# tulip_breakout.net
KiCad netlist of a schematic drawn in EAGLE
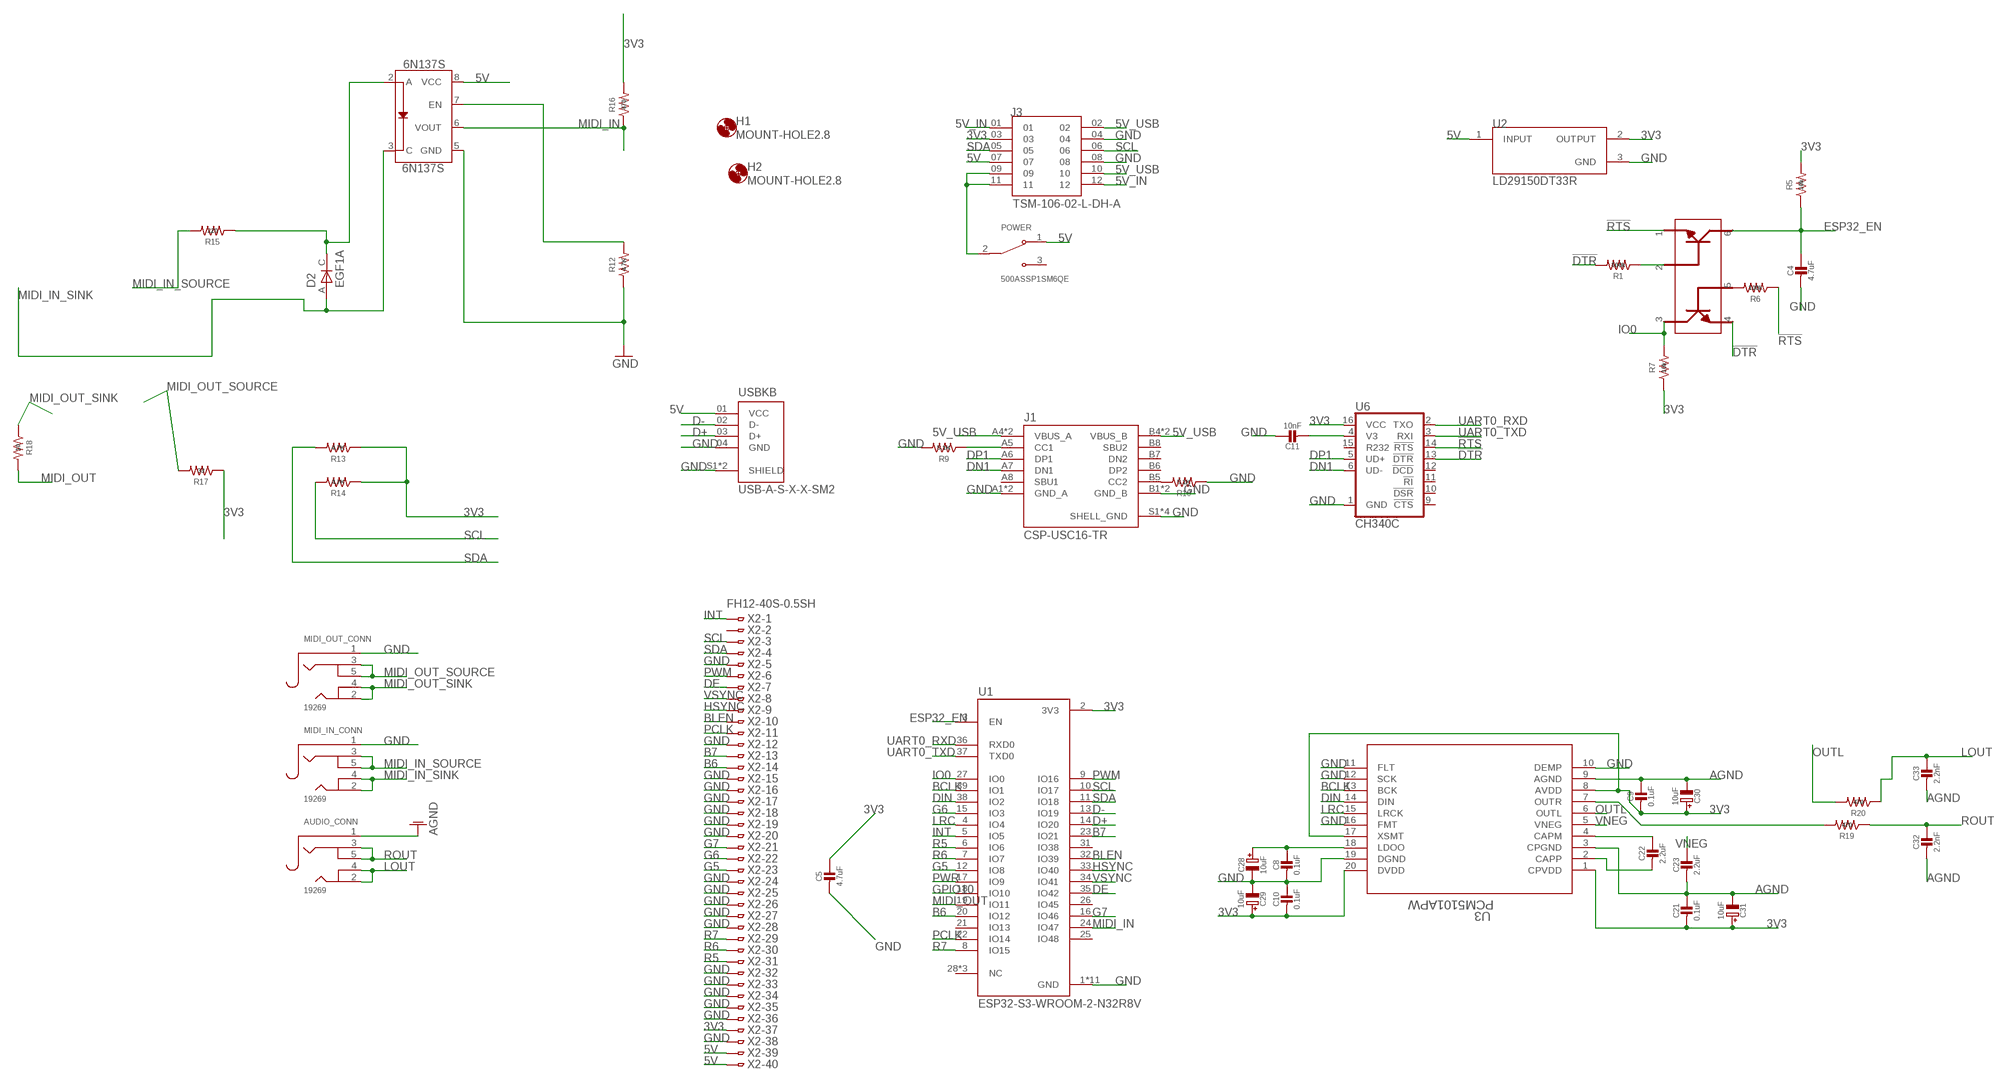
[diagram p0: schematic, sheet 1]

(export (version "E")
  (design (tool "Eeschema 10.0.6"))
  (components
    (comp (ref "6N137S")
      (value "6N137S")
      (footprint "eagle-import:8-SMD")
      (fields (field (name "MF") "Lite-On Inc."))
      (libsource (lib "eagle-import") (part "6N137S"))
    )
    (comp (ref "AUDIO_CONN")
      (value "19269")
      (footprint "eagle-import:4UCONN_19269")
      (libsource (lib "eagle-import") (part "AUDIO_3.5MMJACK"))
    )
    (comp (ref "C4")
      (value "4.7uF")
      (footprint "eagle-import:0805-NO")
      (libsource (lib "eagle-import") (part "CAP_CERAMIC0805-NOOUTLINE"))
    )
    (comp (ref "C5")
      (value "4.7uF")
      (footprint "eagle-import:0805-NO")
      (libsource (lib "eagle-import") (part "CAP_CERAMIC0805-NOOUTLINE"))
    )
    (comp (ref "C8")
      (value "0.1uF")
      (footprint "eagle-import:0805-NO")
      (libsource (lib "eagle-import") (part "CAP_CERAMIC0805-NOOUTLINE"))
    )
    (comp (ref "C9")
      (value "0.1uF")
      (footprint "eagle-import:0805-NO")
      (libsource (lib "eagle-import") (part "CAP_CERAMIC0805-NOOUTLINE"))
    )
    (comp (ref "C10")
      (value "0.1uF")
      (footprint "eagle-import:0805-NO")
      (libsource (lib "eagle-import") (part "CAP_CERAMIC0805-NOOUTLINE"))
    )
    (comp (ref "C11")
      (value "10nF")
      (footprint "eagle-import:0805-NO")
      (libsource (lib "eagle-import") (part "CAP_CERAMIC0805-NOOUTLINE"))
    )
    (comp (ref "C21")
      (value "0.1uF")
      (footprint "eagle-import:0805-NO")
      (libsource (lib "eagle-import") (part "CAP_CERAMIC0805-NOOUTLINE"))
    )
    (comp (ref "C22")
      (value "2.2uF")
      (footprint "eagle-import:0805-NO")
      (libsource (lib "eagle-import") (part "CAP_CERAMIC0805-NOOUTLINE"))
    )
    (comp (ref "C23")
      (value "2.2uF")
      (footprint "eagle-import:0805-NO")
      (libsource (lib "eagle-import") (part "CAP_CERAMIC0805-NOOUTLINE"))
    )
    (comp (ref "C28")
      (value "10uF")
      (footprint "eagle-import:PANASONIC_C")
      (libsource (lib "eagle-import") (part "CAP_ELECTROLYTICPANASONIC_C"))
    )
    (comp (ref "C29")
      (value "10uF")
      (footprint "eagle-import:PANASONIC_C")
      (libsource (lib "eagle-import") (part "CAP_ELECTROLYTICPANASONIC_C"))
    )
    (comp (ref "C30")
      (value "10uF")
      (footprint "eagle-import:PANASONIC_C")
      (libsource (lib "eagle-import") (part "CAP_ELECTROLYTICPANASONIC_C"))
    )
    (comp (ref "C31")
      (value "10uF")
      (footprint "eagle-import:PANASONIC_C")
      (libsource (lib "eagle-import") (part "CAP_ELECTROLYTICPANASONIC_C"))
    )
    (comp (ref "C32")
      (value "2.2nF")
      (footprint "eagle-import:0805-NO")
      (libsource (lib "eagle-import") (part "CAP_CERAMIC0805-NOOUTLINE"))
    )
    (comp (ref "C33")
      (value "2.2nF")
      (footprint "eagle-import:0805-NO")
      (libsource (lib "eagle-import") (part "CAP_CERAMIC0805-NOOUTLINE"))
    )
    (comp (ref "D2")
      (value "EGF1A")
      (footprint "eagle-import:DIOM449X264X300L114X135N")
      (fields (field (name "MF") "ON Semiconductor"))
      (libsource (lib "eagle-import") (part "EGF1A"))
    )
    (comp (ref "H1")
      (value "MOUNT-HOLE2.8")
      (footprint "eagle-import:2,8")
      (libsource (lib "eagle-import") (part "MOUNT-HOLE2.8"))
    )
    (comp (ref "H2")
      (value "MOUNT-HOLE2.8")
      (footprint "eagle-import:2,8")
      (libsource (lib "eagle-import") (part "MOUNT-HOLE2.8"))
    )
    (comp (ref "J1")
      (value "CSP-USC16-TR")
      (footprint "eagle-import:VALCON_CSP-USC16-TR")
      (fields (field (name "MF") "Valcon"))
      (libsource (lib "eagle-import") (part "CSP-USC16-TR"))
    )
    (comp (ref "J3")
      (value "TSM-106-02-L-DH-A")
      (footprint "eagle-import:SAMTEC_TSM-106-02-L-DH-A")
      (fields (field (name "DIGI-KEY_PART_NUMBER") "612-TSM-106-02-L-DH-A-ND") (field (name "MF") "Samtec"))
      (libsource (lib "eagle-import") (part "TSM-106-02-L-DH-A"))
    )
    (comp (ref "MIDI_IN_CONN")
      (value "19269")
      (footprint "eagle-import:4UCONN_19269")
      (libsource (lib "eagle-import") (part "AUDIO_3.5MMJACK"))
    )
    (comp (ref "MIDI_OUT_CONN")
      (value "19269")
      (footprint "eagle-import:4UCONN_19269")
      (libsource (lib "eagle-import") (part "AUDIO_3.5MMJACK"))
    )
    (comp (ref "POWER")
      (value "500ASSP1SM6QE")
      (footprint "eagle-import:SW_500ASSP1SM6QE")
      (fields (field (name "DIGI-KEY_PART_NUMBER") "EG5810TR-ND") (field (name "MF") "E-Switch"))
      (libsource (lib "eagle-import") (part "500ASSP1SM6QE"))
    )
    (comp (ref "R1")
      (value "100k")
      (footprint "eagle-import:R0805")
      (libsource (lib "eagle-import") (part "R-US_R0805"))
    )
    (comp (ref "R5")
      (value "10k")
      (footprint "eagle-import:R0805")
      (libsource (lib "eagle-import") (part "R-US_R0805"))
    )
    (comp (ref "R6")
      (value "100k")
      (footprint "eagle-import:R0805")
      (libsource (lib "eagle-import") (part "R-US_R0805"))
    )
    (comp (ref "R7")
      (value "10k")
      (footprint "eagle-import:R0805")
      (libsource (lib "eagle-import") (part "R-US_R0805"))
    )
    (comp (ref "R9")
      (value "5.1K")
      (footprint "eagle-import:R0805")
      (libsource (lib "eagle-import") (part "R-US_R0805"))
    )
    (comp (ref "R10")
      (value "5.1K")
      (footprint "eagle-import:R0805")
      (libsource (lib "eagle-import") (part "R-US_R0805"))
    )
    (comp (ref "R12")
      (value "4.7K")
      (footprint "eagle-import:R0805")
      (libsource (lib "eagle-import") (part "R-US_R0805"))
    )
    (comp (ref "R13")
      (value "4.7K")
      (footprint "eagle-import:R0805")
      (libsource (lib "eagle-import") (part "R-US_R0805"))
    )
    (comp (ref "R14")
      (value "4.7K")
      (footprint "eagle-import:R0805")
      (libsource (lib "eagle-import") (part "R-US_R0805"))
    )
    (comp (ref "R15")
      (value "220")
      (footprint "eagle-import:R0805")
      (libsource (lib "eagle-import") (part "R-US_R0805"))
    )
    (comp (ref "R16")
      (value "470")
      (footprint "eagle-import:R0805")
      (libsource (lib "eagle-import") (part "R-US_R0805"))
    )
    (comp (ref "R17")
      (value "33")
      (footprint "eagle-import:R0805")
      (libsource (lib "eagle-import") (part "R-US_R0805"))
    )
    (comp (ref "R18")
      (value "10")
      (footprint "eagle-import:R0805")
      (libsource (lib "eagle-import") (part "R-US_R0805"))
    )
    (comp (ref "R19")
      (value "470")
      (footprint "eagle-import:R0805")
      (libsource (lib "eagle-import") (part "R-US_R0805"))
    )
    (comp (ref "R20")
      (value "470")
      (footprint "eagle-import:R0805")
      (libsource (lib "eagle-import") (part "R-US_R0805"))
    )
    (comp (ref "RESET")
      (value "MBT3904DW1T1G")
      (footprint "eagle-import:SOT236")
      (fields (field (name "MF") "ON Semiconductor"))
      (libsource (lib "eagle-import") (part "MBT3904DW1T1G"))
    )
    (comp (ref "U1")
      (value "ESP32-S3-WROOM-2-N32R8V")
      (footprint "eagle-import:XCVR_ESP32-S3-WROOM-2-N32R8V")
      (fields (field (name "MF") "Espressif Systems"))
      (libsource (lib "eagle-import") (part "ESP32-S3-WROOM-2-N32R8V"))
    )
    (comp (ref "U2")
      (value "LD29150DT33R")
      (footprint "eagle-import:DPAK456P972X240-3N")
      (fields (field (name "DIGI-KEY_PART_NUMBER") "497-1496-2-ND") (field (name "MF") "STMicroelectronics"))
      (libsource (lib "eagle-import") (part "LD29150DT33R"))
    )
    (comp (ref "U3")
      (value "PCM5101APW")
      (footprint "eagle-import:PW20_TEX")
      (fields (field (name "COPYRIGHT") "Copyright (C) 2022 Ultra Librarian. All rights reserved."))
      (libsource (lib "eagle-import") (part "PCM5101APW"))
    )
    (comp (ref "U6")
      (value "CH340C")
      (footprint "eagle-import:SO016")
      (libsource (lib "eagle-import") (part "CH340C"))
    )
    (comp (ref "USBKB")
      (value "USB-A-S-X-X-SM2")
      (footprint "eagle-import:SAMTEC_USB-A-S-X-X-SM2")
      (fields (field (name "MF") "Samtec") (field (name "MP") "USB-A-S-F-W-SM2-TR"))
      (libsource (lib "eagle-import") (part "USB-A-S-X-X-SM2"))
    )
    (comp (ref "X2")
      (value "FH12-40S-0.5SH")
      (footprint "eagle-import:FH12-40S-0.5SH")
      (fields (field (name "MPN") "FH12-40S-0.5SH(55)"))
      (libsource (lib "eagle-import") (part "FH12-40S-0.5SH"))
    )
  )
  (nets
    (net (code "1") (name "/3V3") (class "Default")
      (node (ref "C10") (pin "2") (pinfunction "2_2") (pintype "passive"))
      (node (ref "C21") (pin "2") (pinfunction "2_2") (pintype "passive"))
      (node (ref "C29") (pin "+") (pinfunction "+_+") (pintype "passive"))
      (node (ref "C30") (pin "+") (pinfunction "+_+") (pintype "passive"))
      (node (ref "C31") (pin "+") (pinfunction "+_+") (pintype "passive"))
      (node (ref "C5") (pin "1") (pinfunction "1_1") (pintype "passive"))
      (node (ref "C9") (pin "2") (pinfunction "2_2") (pintype "passive"))
      (node (ref "J3") (pin "03") (pinfunction "03_03") (pintype "passive"))
      (node (ref "R13") (pin "1") (pinfunction "1_1") (pintype "passive"))
      (node (ref "R14") (pin "1") (pinfunction "1_1") (pintype "passive"))
      (node (ref "R16") (pin "2") (pinfunction "2_2") (pintype "passive"))
      (node (ref "R17") (pin "1") (pinfunction "1_1") (pintype "passive"))
      (node (ref "R5") (pin "2") (pinfunction "2_2") (pintype "passive"))
      (node (ref "R7") (pin "1") (pinfunction "1_1") (pintype "passive"))
      (node (ref "U1") (pin "2") (pinfunction "3V3_2") (pintype "power_in"))
      (node (ref "U2") (pin "2") (pinfunction "OUTPUT_2") (pintype "output"))
      (node (ref "U3") (pin "1") (pinfunction "CPVDD_1") (pintype "power_in"))
      (node (ref "U3") (pin "17") (pinfunction "XSMT_17") (pintype "input"))
      (node (ref "U3") (pin "20") (pinfunction "DVDD_20") (pintype "power_in"))
      (node (ref "U3") (pin "8") (pinfunction "AVDD_8") (pintype "power_in"))
      (node (ref "U6") (pin "16") (pinfunction "VCC_16") (pintype "bidirectional"))
      (node (ref "X2") (pin "37") (pinfunction "1_37") (pintype "passive"))
    )
    (net (code "2") (name "/5V") (class "Default")
      (node (ref "6N137S") (pin "8") (pinfunction "VCC_8") (pintype "bidirectional"))
      (node (ref "J3") (pin "07") (pinfunction "07_07") (pintype "passive"))
      (node (ref "POWER") (pin "1") (pinfunction "NC_1") (pintype "passive"))
      (node (ref "U2") (pin "1") (pinfunction "INPUT_1") (pintype "input"))
      (node (ref "USBKB") (pin "01") (pinfunction "VCC_01") (pintype "power_in"))
      (node (ref "X2") (pin "39") (pinfunction "1_39") (pintype "passive"))
      (node (ref "X2") (pin "40") (pinfunction "1_40") (pintype "passive"))
    )
    (net (code "3") (name "/5V_IN") (class "Default")
      (node (ref "J3") (pin "01") (pinfunction "01_01") (pintype "passive"))
      (node (ref "J3") (pin "12") (pinfunction "12_12") (pintype "passive"))
    )
    (net (code "4") (name "/5V_USB") (class "Default")
      (node (ref "J1") (pin "A4") (pinfunction "VBUS_A_A4") (pintype "power_in"))
      (node (ref "J1") (pin "A9") (pinfunction "VBUS_A_A9") (pintype "power_in"))
      (node (ref "J1") (pin "B4") (pinfunction "VBUS_B_B4") (pintype "power_in"))
      (node (ref "J1") (pin "B9") (pinfunction "VBUS_B_B9") (pintype "power_in"))
      (node (ref "J3") (pin "02") (pinfunction "02_02") (pintype "passive"))
      (node (ref "J3") (pin "10") (pinfunction "10_10") (pintype "passive"))
    )
    (net (code "5") (name "/B6") (class "Default")
      (node (ref "U1") (pin "20") (pinfunction "IO12_20") (pintype "bidirectional"))
      (node (ref "X2") (pin "14") (pinfunction "1_14") (pintype "passive"))
    )
    (net (code "6") (name "/B7") (class "Default")
      (node (ref "U1") (pin "23") (pinfunction "IO21_23") (pintype "bidirectional"))
      (node (ref "X2") (pin "13") (pinfunction "1_13") (pintype "passive"))
    )
    (net (code "7") (name "/BCLK") (class "Default")
      (node (ref "U1") (pin "39") (pinfunction "IO1_39") (pintype "bidirectional"))
      (node (ref "U3") (pin "13") (pinfunction "BCK_13") (pintype "input"))
    )
    (net (code "8") (name "/BLEN") (class "Default")
      (node (ref "U1") (pin "32") (pinfunction "IO39_32") (pintype "bidirectional"))
      (node (ref "X2") (pin "10") (pinfunction "1_10") (pintype "passive"))
    )
    (net (code "9") (name "/D+") (class "Default")
      (node (ref "U1") (pin "14") (pinfunction "IO20_14") (pintype "bidirectional"))
      (node (ref "USBKB") (pin "03") (pinfunction "D+_03") (pintype "bidirectional"))
    )
    (net (code "10") (name "/D-") (class "Default")
      (node (ref "U1") (pin "13") (pinfunction "IO19_13") (pintype "bidirectional"))
      (node (ref "USBKB") (pin "02") (pinfunction "D-_02") (pintype "bidirectional"))
    )
    (net (code "11") (name "/DE") (class "Default")
      (node (ref "U1") (pin "35") (pinfunction "IO42_35") (pintype "bidirectional"))
      (node (ref "X2") (pin "7") (pinfunction "1_7") (pintype "passive"))
    )
    (net (code "12") (name "/DIN") (class "Default")
      (node (ref "U1") (pin "38") (pinfunction "IO2_38") (pintype "bidirectional"))
      (node (ref "U3") (pin "14") (pinfunction "DIN_14") (pintype "input"))
    )
    (net (code "13") (name "/DN1") (class "Default")
      (node (ref "J1") (pin "A7") (pinfunction "DN1_A7") (pintype "bidirectional"))
      (node (ref "U6") (pin "6") (pinfunction "UD-_6") (pintype "bidirectional"))
    )
    (net (code "14") (name "/DP1") (class "Default")
      (node (ref "J1") (pin "A6") (pinfunction "DP1_A6") (pintype "bidirectional"))
      (node (ref "U6") (pin "5") (pinfunction "UD+_5") (pintype "bidirectional"))
    )
    (net (code "15") (name "/ESP32_EN") (class "Default")
      (node (ref "C4") (pin "1") (pinfunction "1_1") (pintype "passive"))
      (node (ref "R5") (pin "1") (pinfunction "1_1") (pintype "passive"))
      (node (ref "RESET") (pin "6") (pinfunction "6_6") (pintype "bidirectional"))
      (node (ref "U1") (pin "3") (pinfunction "EN_3") (pintype "input"))
    )
    (net (code "16") (name "/G5") (class "Default")
      (node (ref "U1") (pin "12") (pinfunction "IO8_12") (pintype "bidirectional"))
      (node (ref "X2") (pin "23") (pinfunction "1_23") (pintype "passive"))
    )
    (net (code "17") (name "/G6") (class "Default")
      (node (ref "U1") (pin "15") (pinfunction "IO3_15") (pintype "bidirectional"))
      (node (ref "X2") (pin "22") (pinfunction "1_22") (pintype "passive"))
    )
    (net (code "18") (name "/G7") (class "Default")
      (node (ref "U1") (pin "16") (pinfunction "IO46_16") (pintype "bidirectional"))
      (node (ref "X2") (pin "21") (pinfunction "1_21") (pintype "passive"))
    )
    (net (code "19") (name "/GPIO10") (class "Default")
      (node (ref "U1") (pin "18") (pinfunction "IO10_18") (pintype "bidirectional"))
    )
    (net (code "20") (name "/HSYNC") (class "Default")
      (node (ref "U1") (pin "33") (pinfunction "IO40_33") (pintype "bidirectional"))
      (node (ref "X2") (pin "9") (pinfunction "1_9") (pintype "passive"))
    )
    (net (code "21") (name "/INT") (class "Default")
      (node (ref "U1") (pin "5") (pinfunction "IO5_5") (pintype "bidirectional"))
      (node (ref "X2") (pin "1") (pinfunction "1_1") (pintype "passive"))
    )
    (net (code "22") (name "/IO0") (class "Default")
      (node (ref "R7") (pin "2") (pinfunction "2_2") (pintype "passive"))
      (node (ref "RESET") (pin "3") (pinfunction "3_3") (pintype "bidirectional"))
      (node (ref "U1") (pin "27") (pinfunction "IO0_27") (pintype "bidirectional"))
    )
    (net (code "23") (name "/LOUT") (class "Default")
      (node (ref "AUDIO_CONN") (pin "2") (pinfunction "P$5_2") (pintype "bidirectional"))
      (node (ref "AUDIO_CONN") (pin "4") (pinfunction "P$4_4") (pintype "bidirectional"))
      (node (ref "C33") (pin "1") (pinfunction "1_1") (pintype "passive"))
      (node (ref "R20") (pin "1") (pinfunction "1_1") (pintype "passive"))
    )
    (net (code "24") (name "/LRC") (class "Default")
      (node (ref "U1") (pin "4") (pinfunction "IO4_4") (pintype "bidirectional"))
      (node (ref "U3") (pin "15") (pinfunction "LRCK_15") (pintype "input"))
    )
    (net (code "25") (name "/MIDI_IN") (class "Default")
      (node (ref "6N137S") (pin "6") (pinfunction "VOUT_6") (pintype "bidirectional"))
      (node (ref "R16") (pin "1") (pinfunction "1_1") (pintype "passive"))
      (node (ref "U1") (pin "24") (pinfunction "IO47_24") (pintype "bidirectional"))
    )
    (net (code "26") (name "/MIDI_IN_SINK") (class "Default")
      (node (ref "6N137S") (pin "3") (pinfunction "C_3") (pintype "bidirectional"))
      (node (ref "D2") (pin "A") (pinfunction "A_A") (pintype "passive"))
      (node (ref "MIDI_IN_CONN") (pin "2") (pinfunction "P$5_2") (pintype "bidirectional"))
      (node (ref "MIDI_IN_CONN") (pin "4") (pinfunction "P$4_4") (pintype "bidirectional"))
    )
    (net (code "27") (name "/MIDI_IN_SOURCE") (class "Default")
      (node (ref "MIDI_IN_CONN") (pin "3") (pinfunction "P$2_3") (pintype "bidirectional"))
      (node (ref "MIDI_IN_CONN") (pin "5") (pinfunction "P$3_5") (pintype "bidirectional"))
      (node (ref "R15") (pin "2") (pinfunction "2_2") (pintype "passive"))
    )
    (net (code "28") (name "/MIDI_OUT") (class "Default")
      (node (ref "R18") (pin "2") (pinfunction "2_2") (pintype "passive"))
      (node (ref "U1") (pin "19") (pinfunction "IO11_19") (pintype "bidirectional"))
    )
    (net (code "29") (name "/MIDI_OUT_SINK") (class "Default")
      (node (ref "MIDI_OUT_CONN") (pin "2") (pinfunction "P$5_2") (pintype "bidirectional"))
      (node (ref "MIDI_OUT_CONN") (pin "4") (pinfunction "P$4_4") (pintype "bidirectional"))
      (node (ref "R18") (pin "1") (pinfunction "1_1") (pintype "passive"))
    )
    (net (code "30") (name "/MIDI_OUT_SOURCE") (class "Default")
      (node (ref "MIDI_OUT_CONN") (pin "3") (pinfunction "P$2_3") (pintype "bidirectional"))
      (node (ref "MIDI_OUT_CONN") (pin "5") (pinfunction "P$3_5") (pintype "bidirectional"))
      (node (ref "R17") (pin "2") (pinfunction "2_2") (pintype "passive"))
    )
    (net (code "31") (name "/OUTL") (class "Default")
      (node (ref "R20") (pin "2") (pinfunction "2_2") (pintype "passive"))
      (node (ref "U3") (pin "6") (pinfunction "OUTL_6") (pintype "output"))
    )
    (net (code "32") (name "/PCLK") (class "Default")
      (node (ref "U1") (pin "22") (pinfunction "IO14_22") (pintype "bidirectional"))
      (node (ref "X2") (pin "11") (pinfunction "1_11") (pintype "passive"))
    )
    (net (code "33") (name "/PWM") (class "Default")
      (node (ref "U1") (pin "9") (pinfunction "IO16_9") (pintype "bidirectional"))
      (node (ref "X2") (pin "6") (pinfunction "1_6") (pintype "passive"))
    )
    (net (code "34") (name "/PWR") (class "Default")
      (node (ref "U1") (pin "17") (pinfunction "IO9_17") (pintype "bidirectional"))
    )
    (net (code "35") (name "/R5") (class "Default")
      (node (ref "U1") (pin "6") (pinfunction "IO6_6") (pintype "bidirectional"))
      (node (ref "X2") (pin "31") (pinfunction "1_31") (pintype "passive"))
    )
    (net (code "36") (name "/R6") (class "Default")
      (node (ref "U1") (pin "7") (pinfunction "IO7_7") (pintype "bidirectional"))
      (node (ref "X2") (pin "30") (pinfunction "1_30") (pintype "passive"))
    )
    (net (code "37") (name "/R7") (class "Default")
      (node (ref "U1") (pin "8") (pinfunction "IO15_8") (pintype "bidirectional"))
      (node (ref "X2") (pin "29") (pinfunction "1_29") (pintype "passive"))
    )
    (net (code "38") (name "/ROUT") (class "Default")
      (node (ref "AUDIO_CONN") (pin "3") (pinfunction "P$2_3") (pintype "bidirectional"))
      (node (ref "AUDIO_CONN") (pin "5") (pinfunction "P$3_5") (pintype "bidirectional"))
      (node (ref "C32") (pin "1") (pinfunction "1_1") (pintype "passive"))
      (node (ref "R19") (pin "1") (pinfunction "1_1") (pintype "passive"))
    )
    (net (code "39") (name "/SCL") (class "Default")
      (node (ref "J3") (pin "06") (pinfunction "06_06") (pintype "passive"))
      (node (ref "R14") (pin "2") (pinfunction "2_2") (pintype "passive"))
      (node (ref "U1") (pin "10") (pinfunction "IO17_10") (pintype "bidirectional"))
      (node (ref "X2") (pin "3") (pinfunction "1_3") (pintype "passive"))
    )
    (net (code "40") (name "/SDA") (class "Default")
      (node (ref "J3") (pin "05") (pinfunction "05_05") (pintype "passive"))
      (node (ref "R13") (pin "2") (pinfunction "2_2") (pintype "passive"))
      (node (ref "U1") (pin "11") (pinfunction "IO18_11") (pintype "bidirectional"))
      (node (ref "X2") (pin "4") (pinfunction "1_4") (pintype "passive"))
    )
    (net (code "41") (name "/UART0_RXD") (class "Default")
      (node (ref "U1") (pin "36") (pinfunction "RXD0_36") (pintype "bidirectional"))
      (node (ref "U6") (pin "2") (pinfunction "TXO_2") (pintype "bidirectional"))
    )
    (net (code "42") (name "/UART0_TXD") (class "Default")
      (node (ref "U1") (pin "37") (pinfunction "TXD0_37") (pintype "bidirectional"))
      (node (ref "U6") (pin "3") (pinfunction "RXI_3") (pintype "bidirectional"))
    )
    (net (code "43") (name "/VNEG") (class "Default")
      (node (ref "C23") (pin "1") (pinfunction "1_1") (pintype "passive"))
      (node (ref "U3") (pin "5") (pinfunction "VNEG_5") (pintype "output"))
    )
    (net (code "44") (name "/VSYNC") (class "Default")
      (node (ref "U1") (pin "34") (pinfunction "IO41_34") (pintype "bidirectional"))
      (node (ref "X2") (pin "8") (pinfunction "1_8") (pintype "passive"))
    )
    (net (code "45") (name "/~{DTR}") (class "Default")
      (node (ref "R1") (pin "2") (pinfunction "2_2") (pintype "passive"))
      (node (ref "RESET") (pin "4") (pinfunction "4_4") (pintype "bidirectional"))
      (node (ref "U6") (pin "13") (pinfunction "~{DTR}_13") (pintype "bidirectional"))
    )
    (net (code "46") (name "/~{RTS}") (class "Default")
      (node (ref "R6") (pin "1") (pinfunction "1_1") (pintype "passive"))
      (node (ref "RESET") (pin "1") (pinfunction "1_1") (pintype "bidirectional"))
      (node (ref "U6") (pin "14") (pinfunction "~{RTS}_14") (pintype "bidirectional"))
    )
    (net (code "47") (name "AGND") (class "Default")
      (node (ref "AUDIO_CONN") (pin "1") (pinfunction "P$1_1") (pintype "bidirectional"))
      (node (ref "C21") (pin "1") (pinfunction "1_1") (pintype "passive"))
      (node (ref "C23") (pin "2") (pinfunction "2_2") (pintype "passive"))
      (node (ref "C30") (pin "-") (pinfunction "-_-") (pintype "passive"))
      (node (ref "C31") (pin "-") (pinfunction "-_-") (pintype "passive"))
      (node (ref "C32") (pin "2") (pinfunction "2_2") (pintype "passive"))
      (node (ref "C33") (pin "2") (pinfunction "2_2") (pintype "passive"))
      (node (ref "C9") (pin "1") (pinfunction "1_1") (pintype "passive"))
      (node (ref "U3") (pin "3") (pinfunction "CPGND_3") (pintype "power_in"))
      (node (ref "U3") (pin "9") (pinfunction "AGND_9") (pintype "power_in"))
    )
    (net (code "48") (name "GND") (class "Default")
      (node (ref "6N137S") (pin "5") (pinfunction "GND_5") (pintype "bidirectional"))
      (node (ref "C10") (pin "1") (pinfunction "1_1") (pintype "passive"))
      (node (ref "C11") (pin "1") (pinfunction "1_1") (pintype "passive"))
      (node (ref "C28") (pin "-") (pinfunction "-_-") (pintype "passive"))
      (node (ref "C29") (pin "-") (pinfunction "-_-") (pintype "passive"))
      (node (ref "C4") (pin "2") (pinfunction "2_2") (pintype "passive"))
      (node (ref "C5") (pin "2") (pinfunction "2_2") (pintype "passive"))
      (node (ref "C8") (pin "2") (pinfunction "2_2") (pintype "passive"))
      (node (ref "J1") (pin "A1") (pinfunction "GND_A_A1") (pintype "power_in"))
      (node (ref "J1") (pin "A12") (pinfunction "GND_A_A12") (pintype "power_in"))
      (node (ref "J1") (pin "B1") (pinfunction "GND_B_B1") (pintype "power_in"))
      (node (ref "J1") (pin "B12") (pinfunction "GND_B_B12") (pintype "power_in"))
      (node (ref "J1") (pin "S1") (pinfunction "SHELL_GND_S1") (pintype "power_in"))
      (node (ref "J1") (pin "S2") (pinfunction "SHELL_GND_S2") (pintype "power_in"))
      (node (ref "J1") (pin "S3") (pinfunction "SHELL_GND_S3") (pintype "power_in"))
      (node (ref "J1") (pin "S4") (pinfunction "SHELL_GND_S4") (pintype "power_in"))
      (node (ref "J3") (pin "04") (pinfunction "04_04") (pintype "passive"))
      (node (ref "J3") (pin "08") (pinfunction "08_08") (pintype "passive"))
      (node (ref "MIDI_IN_CONN") (pin "1") (pinfunction "P$1_1") (pintype "bidirectional"))
      (node (ref "MIDI_OUT_CONN") (pin "1") (pinfunction "P$1_1") (pintype "bidirectional"))
      (node (ref "R10") (pin "1") (pinfunction "1_1") (pintype "passive"))
      (node (ref "R12") (pin "1") (pinfunction "1_1") (pintype "passive"))
      (node (ref "R9") (pin "2") (pinfunction "2_2") (pintype "passive"))
      (node (ref "U1") (pin "1") (pinfunction "GND_1") (pintype "power_in"))
      (node (ref "U1") (pin "40") (pinfunction "GND_40") (pintype "power_in"))
      (node (ref "U1") (pin "41_1") (pinfunction "GND_41_1") (pintype "power_in"))
      (node (ref "U1") (pin "41_2") (pinfunction "GND_41_2") (pintype "power_in"))
      (node (ref "U1") (pin "41_3") (pinfunction "GND_41_3") (pintype "power_in"))
      (node (ref "U1") (pin "41_4") (pinfunction "GND_41_4") (pintype "power_in"))
      (node (ref "U1") (pin "41_5") (pinfunction "GND_41_5") (pintype "power_in"))
      (node (ref "U1") (pin "41_6") (pinfunction "GND_41_6") (pintype "power_in"))
      (node (ref "U1") (pin "41_7") (pinfunction "GND_41_7") (pintype "power_in"))
      (node (ref "U1") (pin "41_8") (pinfunction "GND_41_8") (pintype "power_in"))
      (node (ref "U1") (pin "41_9") (pinfunction "GND_41_9") (pintype "power_in"))
      (node (ref "U2") (pin "3") (pinfunction "GND_3") (pintype "power_in"))
      (node (ref "U3") (pin "10") (pinfunction "DEMP_10") (pintype "input"))
      (node (ref "U3") (pin "11") (pinfunction "FLT_11") (pintype "input"))
      (node (ref "U3") (pin "12") (pinfunction "SCK_12") (pintype "input"))
      (node (ref "U3") (pin "16") (pinfunction "FMT_16") (pintype "input"))
      (node (ref "U3") (pin "19") (pinfunction "DGND_19") (pintype "power_in"))
      (node (ref "U6") (pin "1") (pinfunction "GND_1") (pintype "bidirectional"))
      (node (ref "USBKB") (pin "04") (pinfunction "GND_04") (pintype "power_in"))
      (node (ref "USBKB") (pin "S1") (pinfunction "SHIELD_S1") (pintype "passive"))
      (node (ref "USBKB") (pin "S2") (pinfunction "SHIELD_S2") (pintype "passive"))
      (node (ref "X2") (pin "12") (pinfunction "1_12") (pintype "passive"))
      (node (ref "X2") (pin "15") (pinfunction "1_15") (pintype "passive"))
      (node (ref "X2") (pin "16") (pinfunction "1_16") (pintype "passive"))
      (node (ref "X2") (pin "17") (pinfunction "1_17") (pintype "passive"))
      (node (ref "X2") (pin "18") (pinfunction "1_18") (pintype "passive"))
      (node (ref "X2") (pin "19") (pinfunction "1_19") (pintype "passive"))
      (node (ref "X2") (pin "20") (pinfunction "1_20") (pintype "passive"))
      (node (ref "X2") (pin "24") (pinfunction "1_24") (pintype "passive"))
      (node (ref "X2") (pin "25") (pinfunction "1_25") (pintype "passive"))
      (node (ref "X2") (pin "26") (pinfunction "1_26") (pintype "passive"))
      (node (ref "X2") (pin "27") (pinfunction "1_27") (pintype "passive"))
      (node (ref "X2") (pin "28") (pinfunction "1_28") (pintype "passive"))
      (node (ref "X2") (pin "32") (pinfunction "1_32") (pintype "passive"))
      (node (ref "X2") (pin "33") (pinfunction "1_33") (pintype "passive"))
      (node (ref "X2") (pin "34") (pinfunction "1_34") (pintype "passive"))
      (node (ref "X2") (pin "35") (pinfunction "1_35") (pintype "passive"))
      (node (ref "X2") (pin "36") (pinfunction "1_36") (pintype "passive"))
      (node (ref "X2") (pin "38") (pinfunction "1_38") (pintype "passive"))
      (node (ref "X2") (pin "5") (pinfunction "1_5") (pintype "passive"))
    )
    (net (code "49") (name "Net-(6N137S-A)") (class "Default")
      (node (ref "6N137S") (pin "2") (pinfunction "A_2") (pintype "bidirectional"))
      (node (ref "D2") (pin "C") (pinfunction "C_C") (pintype "passive"))
      (node (ref "R15") (pin "1") (pinfunction "1_1") (pintype "passive"))
    )
    (net (code "50") (name "Net-(6N137S-EN)") (class "Default")
      (node (ref "6N137S") (pin "7") (pinfunction "EN_7") (pintype "bidirectional"))
      (node (ref "R12") (pin "2") (pinfunction "2_2") (pintype "passive"))
    )
    (net (code "51") (name "Net-(J1-CC1)") (class "Default")
      (node (ref "J1") (pin "A5") (pinfunction "CC1_A5") (pintype "bidirectional"))
      (node (ref "R9") (pin "1") (pinfunction "1_1") (pintype "passive"))
    )
    (net (code "52") (name "Net-(J1-CC2)") (class "Default")
      (node (ref "J1") (pin "B5") (pinfunction "CC2_B5") (pintype "bidirectional"))
      (node (ref "R10") (pin "2") (pinfunction "2_2") (pintype "passive"))
    )
    (net (code "53") (name "Net-(POWER-COM)") (class "Default")
      (node (ref "J3") (pin "09") (pinfunction "09_09") (pintype "passive"))
      (node (ref "J3") (pin "11") (pinfunction "11_11") (pintype "passive"))
      (node (ref "POWER") (pin "2") (pinfunction "COM_2") (pintype "passive"))
    )
    (net (code "54") (name "Net-(R1-Pad1)") (class "Default")
      (node (ref "R1") (pin "1") (pinfunction "1_1") (pintype "passive"))
      (node (ref "RESET") (pin "2") (pinfunction "2_2") (pintype "bidirectional"))
    )
    (net (code "55") (name "Net-(R6-Pad2)") (class "Default")
      (node (ref "R6") (pin "2") (pinfunction "2_2") (pintype "passive"))
      (node (ref "RESET") (pin "5") (pinfunction "5_5") (pintype "bidirectional"))
    )
    (net (code "56") (name "Net-(U3-CAPM)") (class "Default")
      (node (ref "C22") (pin "1") (pinfunction "1_1") (pintype "passive"))
      (node (ref "U3") (pin "4") (pinfunction "CAPM_4") (pintype "output"))
    )
    (net (code "57") (name "Net-(U3-CAPP)") (class "Default")
      (node (ref "C22") (pin "2") (pinfunction "2_2") (pintype "passive"))
      (node (ref "U3") (pin "2") (pinfunction "CAPP_2") (pintype "output"))
    )
    (net (code "58") (name "Net-(U3-LDOO)") (class "Default")
      (node (ref "C28") (pin "+") (pinfunction "+_+") (pintype "passive"))
      (node (ref "C8") (pin "1") (pinfunction "1_1") (pintype "passive"))
      (node (ref "U3") (pin "18") (pinfunction "LDOO_18") (pintype "power_in"))
    )
    (net (code "59") (name "Net-(U3-OUTR)") (class "Default")
      (node (ref "R19") (pin "2") (pinfunction "2_2") (pintype "passive"))
      (node (ref "U3") (pin "7") (pinfunction "OUTR_7") (pintype "output"))
    )
    (net (code "60") (name "Net-(U6-V3)") (class "Default")
      (node (ref "C11") (pin "2") (pinfunction "2_2") (pintype "passive"))
      (node (ref "U6") (pin "4") (pinfunction "V3_4") (pintype "bidirectional"))
    )
    (net (code "61") (name "unconnected-(J1-DN2-PadB7)") (class "Default")
      (node (ref "J1") (pin "B7") (pinfunction "DN2_B7") (pintype "bidirectional"))
    )
    (net (code "62") (name "unconnected-(J1-DP2-PadB6)") (class "Default")
      (node (ref "J1") (pin "B6") (pinfunction "DP2_B6") (pintype "bidirectional"))
    )
    (net (code "63") (name "unconnected-(J1-SBU1-PadA8)") (class "Default")
      (node (ref "J1") (pin "A8") (pinfunction "SBU1_A8") (pintype "bidirectional"))
    )
    (net (code "64") (name "unconnected-(J1-SBU2-PadB8)") (class "Default")
      (node (ref "J1") (pin "B8") (pinfunction "SBU2_B8") (pintype "bidirectional"))
    )
    (net (code "65") (name "unconnected-(POWER-NO-Pad3)") (class "Default")
      (node (ref "POWER") (pin "3") (pinfunction "NO_3") (pintype "passive"))
    )
    (net (code "66") (name "unconnected-(U1-IO13-Pad21)") (class "Default")
      (node (ref "U1") (pin "21") (pinfunction "IO13_21") (pintype "bidirectional"))
    )
    (net (code "67") (name "unconnected-(U1-IO38-Pad31)") (class "Default")
      (node (ref "U1") (pin "31") (pinfunction "IO38_31") (pintype "bidirectional"))
    )
    (net (code "68") (name "unconnected-(U1-IO45-Pad26)") (class "Default")
      (node (ref "U1") (pin "26") (pinfunction "IO45_26") (pintype "bidirectional"))
    )
    (net (code "69") (name "unconnected-(U1-IO48-Pad25)") (class "Default")
      (node (ref "U1") (pin "25") (pinfunction "IO48_25") (pintype "bidirectional"))
    )
    (net (code "70") (name "unconnected-(U1-NC-Pad28)") (class "Default")
      (node (ref "U1") (pin "28") (pinfunction "NC_28") (pintype "no_connect"))
    )
    (net (code "71") (name "unconnected-(U1-NC-Pad29)") (class "Default")
      (node (ref "U1") (pin "29") (pinfunction "NC_29") (pintype "no_connect"))
    )
    (net (code "72") (name "unconnected-(U1-NC-Pad30)") (class "Default")
      (node (ref "U1") (pin "30") (pinfunction "NC_30") (pintype "no_connect"))
    )
    (net (code "73") (name "unconnected-(U6-R232-Pad15)") (class "Default")
      (node (ref "U6") (pin "15") (pinfunction "R232_15") (pintype "bidirectional"))
    )
    (net (code "74") (name "unconnected-(U6-~{CTS}-Pad9)") (class "Default")
      (node (ref "U6") (pin "9") (pinfunction "~{CTS}_9") (pintype "bidirectional"))
    )
    (net (code "75") (name "unconnected-(U6-~{DCD}-Pad12)") (class "Default")
      (node (ref "U6") (pin "12") (pinfunction "~{DCD}_12") (pintype "bidirectional"))
    )
    (net (code "76") (name "unconnected-(U6-~{DSR}-Pad10)") (class "Default")
      (node (ref "U6") (pin "10") (pinfunction "~{DSR}_10") (pintype "bidirectional"))
    )
    (net (code "77") (name "unconnected-(U6-~{RI}-Pad11)") (class "Default")
      (node (ref "U6") (pin "11") (pinfunction "~{RI}_11") (pintype "bidirectional"))
    )
    (net (code "78") (name "unconnected-(X2L-1-Pad2)") (class "Default")
      (node (ref "X2") (pin "2") (pinfunction "1_2") (pintype "passive"))
    )
  )
)
